# Electronics_Design_V2_v8.net
KiCad netlist of a schematic drawn in EAGLE
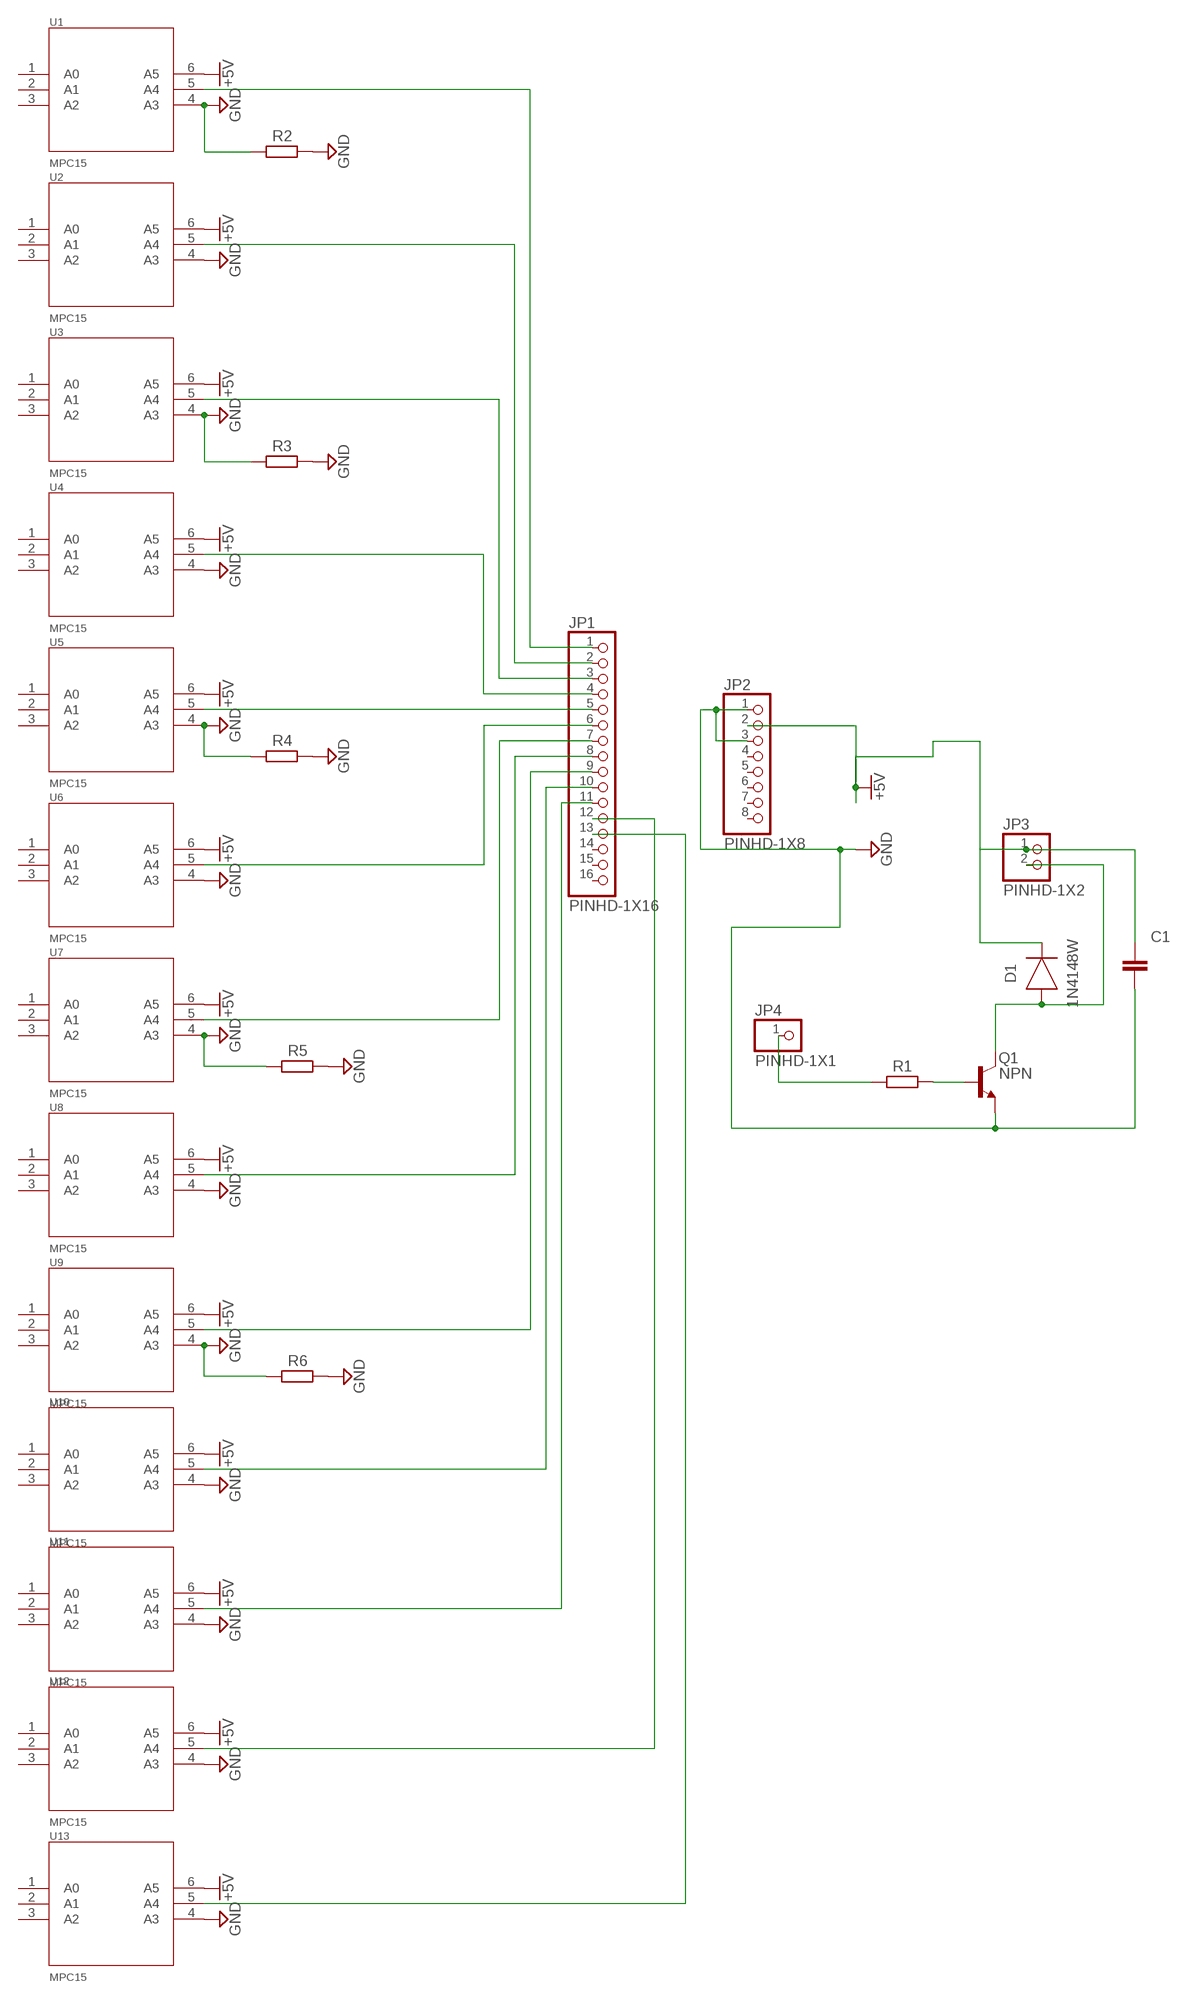
[diagram p0: schematic, sheet 1]

(export (version "E")
  (design (tool "Eeschema 10.0.6"))
  (components
    (comp (ref "C1")
      (value "C_CHIP-1206(3216-METRIC)")
      (footprint "eagle-import:CAPC3216X135")
      (libsource (lib "eagle-import") (part "CCHIP-1206(3216-METRIC)_"))
    )
    (comp (ref "D1")
      (value "1N4148W")
      (footprint "eagle-import:SOD3715X135")
      (fields (field (name "MANUFACTURER") "Diodes Incorporated"))
      (libsource (lib "eagle-import") (part "DIODE__SOD123G1N4148W-7-F"))
    )
    (comp (ref "JP1")
      (value "PINHD-1X16")
      (footprint "eagle-import:1X16")
      (libsource (lib "eagle-import") (part "PINHD-1X16"))
    )
    (comp (ref "JP2")
      (value "PINHD-1X8")
      (footprint "eagle-import:1X08")
      (libsource (lib "eagle-import") (part "PINHD-1X8"))
    )
    (comp (ref "JP3")
      (value "PINHD-1X2")
      (footprint "eagle-import:1X02")
      (libsource (lib "eagle-import") (part "PINHD-1X2"))
    )
    (comp (ref "JP4")
      (value "PINHD-1X1")
      (footprint "eagle-import:1X01")
      (libsource (lib "eagle-import") (part "PINHD-1X1"))
    )
    (comp (ref "Q1")
      (value "NPN")
      (footprint "eagle-import:SC59")
      (libsource (lib "eagle-import") (part "NPNSC-59_"))
    )
    (comp (ref "R1")
      (value "R_CHIP-1206(3216-METRIC)")
      (footprint "eagle-import:RESC3216X70")
      (libsource (lib "eagle-import") (part "RCHIP-1206(3216-METRIC)_"))
    )
    (comp (ref "R2")
      (value "R_CHIP-1206(3216-METRIC)")
      (footprint "eagle-import:RESC3216X70")
      (libsource (lib "eagle-import") (part "RCHIP-1206(3216-METRIC)_"))
    )
    (comp (ref "R3")
      (value "R_CHIP-1206(3216-METRIC)")
      (footprint "eagle-import:RESC3216X70")
      (libsource (lib "eagle-import") (part "RCHIP-1206(3216-METRIC)_"))
    )
    (comp (ref "R4")
      (value "R_CHIP-1206(3216-METRIC)")
      (footprint "eagle-import:RESC3216X70")
      (libsource (lib "eagle-import") (part "RCHIP-1206(3216-METRIC)_"))
    )
    (comp (ref "R5")
      (value "R_CHIP-1206(3216-METRIC)")
      (footprint "eagle-import:RESC3216X70")
      (libsource (lib "eagle-import") (part "RCHIP-1206(3216-METRIC)_"))
    )
    (comp (ref "R6")
      (value "R_CHIP-1206(3216-METRIC)")
      (footprint "eagle-import:RESC3216X70")
      (libsource (lib "eagle-import") (part "RCHIP-1206(3216-METRIC)_"))
    )
    (comp (ref "U1")
      (value "MPC15")
      (footprint "eagle-import:DIP1000W53P254L850H340Q6B")
      (libsource (lib "eagle-import") (part "MPC15"))
    )
    (comp (ref "U2")
      (value "MPC15")
      (footprint "eagle-import:DIP1000W53P254L850H340Q6B")
      (libsource (lib "eagle-import") (part "MPC15"))
    )
    (comp (ref "U3")
      (value "MPC15")
      (footprint "eagle-import:DIP1000W53P254L850H340Q6B")
      (libsource (lib "eagle-import") (part "MPC15"))
    )
    (comp (ref "U4")
      (value "MPC15")
      (footprint "eagle-import:DIP1000W53P254L850H340Q6B")
      (libsource (lib "eagle-import") (part "MPC15"))
    )
    (comp (ref "U5")
      (value "MPC15")
      (footprint "eagle-import:DIP1000W53P254L850H340Q6B")
      (libsource (lib "eagle-import") (part "MPC15"))
    )
    (comp (ref "U6")
      (value "MPC15")
      (footprint "eagle-import:DIP1000W53P254L850H340Q6B")
      (libsource (lib "eagle-import") (part "MPC15"))
    )
    (comp (ref "U7")
      (value "MPC15")
      (footprint "eagle-import:DIP1000W53P254L850H340Q6B")
      (libsource (lib "eagle-import") (part "MPC15"))
    )
    (comp (ref "U8")
      (value "MPC15")
      (footprint "eagle-import:DIP1000W53P254L850H340Q6B")
      (libsource (lib "eagle-import") (part "MPC15"))
    )
    (comp (ref "U9")
      (value "MPC15")
      (footprint "eagle-import:DIP1000W53P254L850H340Q6B")
      (libsource (lib "eagle-import") (part "MPC15"))
    )
    (comp (ref "U10")
      (value "MPC15")
      (footprint "eagle-import:DIP1000W53P254L850H340Q6B")
      (libsource (lib "eagle-import") (part "MPC15"))
    )
    (comp (ref "U11")
      (value "MPC15")
      (footprint "eagle-import:DIP1000W53P254L850H340Q6B")
      (libsource (lib "eagle-import") (part "MPC15"))
    )
    (comp (ref "U12")
      (value "MPC15")
      (footprint "eagle-import:DIP1000W53P254L850H340Q6B")
      (libsource (lib "eagle-import") (part "MPC15"))
    )
    (comp (ref "U13")
      (value "MPC15")
      (footprint "eagle-import:DIP1000W53P254L850H340Q6B")
      (libsource (lib "eagle-import") (part "MPC15"))
    )
  )
  (nets
    (net (code "1") (name "+5V") (class "Default")
      (node (ref "C1") (pin "1") (pinfunction "1_1") (pintype "passive"))
      (node (ref "D1") (pin "1") (pinfunction "C_1") (pintype "passive"))
      (node (ref "JP2") (pin "2") (pinfunction "2_2") (pintype "passive"))
      (node (ref "JP3") (pin "1") (pinfunction "1_1") (pintype "passive"))
      (node (ref "U1") (pin "6") (pinfunction "A5_6") (pintype "power_in"))
      (node (ref "U10") (pin "6") (pinfunction "A5_6") (pintype "power_in"))
      (node (ref "U11") (pin "6") (pinfunction "A5_6") (pintype "power_in"))
      (node (ref "U12") (pin "6") (pinfunction "A5_6") (pintype "power_in"))
      (node (ref "U13") (pin "6") (pinfunction "A5_6") (pintype "power_in"))
      (node (ref "U2") (pin "6") (pinfunction "A5_6") (pintype "power_in"))
      (node (ref "U3") (pin "6") (pinfunction "A5_6") (pintype "power_in"))
      (node (ref "U4") (pin "6") (pinfunction "A5_6") (pintype "power_in"))
      (node (ref "U5") (pin "6") (pinfunction "A5_6") (pintype "power_in"))
      (node (ref "U6") (pin "6") (pinfunction "A5_6") (pintype "power_in"))
      (node (ref "U7") (pin "6") (pinfunction "A5_6") (pintype "power_in"))
      (node (ref "U8") (pin "6") (pinfunction "A5_6") (pintype "power_in"))
      (node (ref "U9") (pin "6") (pinfunction "A5_6") (pintype "power_in"))
    )
    (net (code "2") (name "GND") (class "Default")
      (node (ref "C1") (pin "2") (pinfunction "2_2") (pintype "passive"))
      (node (ref "JP2") (pin "1") (pinfunction "1_1") (pintype "passive"))
      (node (ref "JP2") (pin "3") (pinfunction "3_3") (pintype "passive"))
      (node (ref "Q1") (pin "E") (pinfunction "E_E") (pintype "passive"))
      (node (ref "R2") (pin "1") (pinfunction "1_1") (pintype "passive"))
      (node (ref "R2") (pin "2") (pinfunction "2_2") (pintype "passive"))
      (node (ref "R3") (pin "1") (pinfunction "1_1") (pintype "passive"))
      (node (ref "R3") (pin "2") (pinfunction "2_2") (pintype "passive"))
      (node (ref "R4") (pin "1") (pinfunction "1_1") (pintype "passive"))
      (node (ref "R4") (pin "2") (pinfunction "2_2") (pintype "passive"))
      (node (ref "R5") (pin "1") (pinfunction "1_1") (pintype "passive"))
      (node (ref "R5") (pin "2") (pinfunction "2_2") (pintype "passive"))
      (node (ref "R6") (pin "1") (pinfunction "1_1") (pintype "passive"))
      (node (ref "R6") (pin "2") (pinfunction "2_2") (pintype "passive"))
      (node (ref "U1") (pin "4") (pinfunction "A3_4") (pintype "power_in"))
      (node (ref "U10") (pin "4") (pinfunction "A3_4") (pintype "power_in"))
      (node (ref "U11") (pin "4") (pinfunction "A3_4") (pintype "power_in"))
      (node (ref "U12") (pin "4") (pinfunction "A3_4") (pintype "power_in"))
      (node (ref "U13") (pin "4") (pinfunction "A3_4") (pintype "power_in"))
      (node (ref "U2") (pin "4") (pinfunction "A3_4") (pintype "power_in"))
      (node (ref "U3") (pin "4") (pinfunction "A3_4") (pintype "power_in"))
      (node (ref "U4") (pin "4") (pinfunction "A3_4") (pintype "power_in"))
      (node (ref "U5") (pin "4") (pinfunction "A3_4") (pintype "power_in"))
      (node (ref "U6") (pin "4") (pinfunction "A3_4") (pintype "power_in"))
      (node (ref "U7") (pin "4") (pinfunction "A3_4") (pintype "power_in"))
      (node (ref "U8") (pin "4") (pinfunction "A3_4") (pintype "power_in"))
      (node (ref "U9") (pin "4") (pinfunction "A3_4") (pintype "power_in"))
    )
    (net (code "3") (name "Net-(D1-A)") (class "Default")
      (node (ref "D1") (pin "2") (pinfunction "A_2") (pintype "passive"))
      (node (ref "JP3") (pin "2") (pinfunction "2_2") (pintype "passive"))
      (node (ref "Q1") (pin "C") (pinfunction "C_C") (pintype "passive"))
    )
    (net (code "4") (name "Net-(JP4-Pad1)") (class "Default")
      (node (ref "JP4") (pin "1") (pinfunction "1_1") (pintype "passive"))
      (node (ref "R1") (pin "1") (pinfunction "1_1") (pintype "passive"))
    )
    (net (code "5") (name "Net-(Q1-PadB)") (class "Default")
      (node (ref "Q1") (pin "B") (pinfunction "B_B") (pintype "passive"))
      (node (ref "R1") (pin "2") (pinfunction "2_2") (pintype "passive"))
    )
    (net (code "6") (name "Net-(U1-A4)") (class "Default")
      (node (ref "JP1") (pin "1") (pinfunction "1_1") (pintype "passive"))
      (node (ref "U1") (pin "5") (pinfunction "A4_5") (pintype "output"))
    )
    (net (code "7") (name "Net-(U2-A4)") (class "Default")
      (node (ref "JP1") (pin "2") (pinfunction "2_2") (pintype "passive"))
      (node (ref "U2") (pin "5") (pinfunction "A4_5") (pintype "output"))
    )
    (net (code "8") (name "Net-(U3-A4)") (class "Default")
      (node (ref "JP1") (pin "3") (pinfunction "3_3") (pintype "passive"))
      (node (ref "U3") (pin "5") (pinfunction "A4_5") (pintype "output"))
    )
    (net (code "9") (name "Net-(U4-A4)") (class "Default")
      (node (ref "JP1") (pin "4") (pinfunction "4_4") (pintype "passive"))
      (node (ref "U4") (pin "5") (pinfunction "A4_5") (pintype "output"))
    )
    (net (code "10") (name "Net-(U5-A4)") (class "Default")
      (node (ref "JP1") (pin "5") (pinfunction "5_5") (pintype "passive"))
      (node (ref "U5") (pin "5") (pinfunction "A4_5") (pintype "output"))
    )
    (net (code "11") (name "Net-(U6-A4)") (class "Default")
      (node (ref "JP1") (pin "6") (pinfunction "6_6") (pintype "passive"))
      (node (ref "U6") (pin "5") (pinfunction "A4_5") (pintype "output"))
    )
    (net (code "12") (name "Net-(U7-A4)") (class "Default")
      (node (ref "JP1") (pin "7") (pinfunction "7_7") (pintype "passive"))
      (node (ref "U7") (pin "5") (pinfunction "A4_5") (pintype "output"))
    )
    (net (code "13") (name "Net-(U8-A4)") (class "Default")
      (node (ref "JP1") (pin "8") (pinfunction "8_8") (pintype "passive"))
      (node (ref "U8") (pin "5") (pinfunction "A4_5") (pintype "output"))
    )
    (net (code "14") (name "Net-(U9-A4)") (class "Default")
      (node (ref "JP1") (pin "9") (pinfunction "9_9") (pintype "passive"))
      (node (ref "U9") (pin "5") (pinfunction "A4_5") (pintype "output"))
    )
    (net (code "15") (name "Net-(U10-A4)") (class "Default")
      (node (ref "JP1") (pin "10") (pinfunction "10_10") (pintype "passive"))
      (node (ref "U10") (pin "5") (pinfunction "A4_5") (pintype "output"))
    )
    (net (code "16") (name "Net-(U11-A4)") (class "Default")
      (node (ref "JP1") (pin "11") (pinfunction "11_11") (pintype "passive"))
      (node (ref "U11") (pin "5") (pinfunction "A4_5") (pintype "output"))
    )
    (net (code "17") (name "Net-(U12-A4)") (class "Default")
      (node (ref "JP1") (pin "12") (pinfunction "12_12") (pintype "passive"))
      (node (ref "U12") (pin "5") (pinfunction "A4_5") (pintype "output"))
    )
    (net (code "18") (name "Net-(U13-A4)") (class "Default")
      (node (ref "JP1") (pin "13") (pinfunction "13_13") (pintype "passive"))
      (node (ref "U13") (pin "5") (pinfunction "A4_5") (pintype "output"))
    )
    (net (code "19") (name "unconnected-(JP1-Pad14)") (class "Default")
      (node (ref "JP1") (pin "14") (pinfunction "14_14") (pintype "passive"))
    )
    (net (code "20") (name "unconnected-(JP1-Pad15)") (class "Default")
      (node (ref "JP1") (pin "15") (pinfunction "15_15") (pintype "passive"))
    )
    (net (code "21") (name "unconnected-(JP1-Pad16)") (class "Default")
      (node (ref "JP1") (pin "16") (pinfunction "16_16") (pintype "passive"))
    )
    (net (code "22") (name "unconnected-(JP2-Pad4)") (class "Default")
      (node (ref "JP2") (pin "4") (pinfunction "4_4") (pintype "passive"))
    )
    (net (code "23") (name "unconnected-(JP2-Pad5)") (class "Default")
      (node (ref "JP2") (pin "5") (pinfunction "5_5") (pintype "passive"))
    )
    (net (code "24") (name "unconnected-(JP2-Pad6)") (class "Default")
      (node (ref "JP2") (pin "6") (pinfunction "6_6") (pintype "passive"))
    )
    (net (code "25") (name "unconnected-(JP2-Pad7)") (class "Default")
      (node (ref "JP2") (pin "7") (pinfunction "7_7") (pintype "passive"))
    )
    (net (code "26") (name "unconnected-(JP2-Pad8)") (class "Default")
      (node (ref "JP2") (pin "8") (pinfunction "8_8") (pintype "passive"))
    )
    (net (code "27") (name "unconnected-(U1-A0-Pad1)") (class "Default")
      (node (ref "U1") (pin "1") (pinfunction "A0_1") (pintype "no_connect"))
    )
    (net (code "28") (name "unconnected-(U1-A1-Pad2)") (class "Default")
      (node (ref "U1") (pin "2") (pinfunction "A1_2") (pintype "no_connect"))
    )
    (net (code "29") (name "unconnected-(U1-A2-Pad3)") (class "Default")
      (node (ref "U1") (pin "3") (pinfunction "A2_3") (pintype "no_connect"))
    )
    (net (code "30") (name "unconnected-(U2-A0-Pad1)") (class "Default")
      (node (ref "U2") (pin "1") (pinfunction "A0_1") (pintype "no_connect"))
    )
    (net (code "31") (name "unconnected-(U2-A1-Pad2)") (class "Default")
      (node (ref "U2") (pin "2") (pinfunction "A1_2") (pintype "no_connect"))
    )
    (net (code "32") (name "unconnected-(U2-A2-Pad3)") (class "Default")
      (node (ref "U2") (pin "3") (pinfunction "A2_3") (pintype "no_connect"))
    )
    (net (code "33") (name "unconnected-(U3-A0-Pad1)") (class "Default")
      (node (ref "U3") (pin "1") (pinfunction "A0_1") (pintype "no_connect"))
    )
    (net (code "34") (name "unconnected-(U3-A1-Pad2)") (class "Default")
      (node (ref "U3") (pin "2") (pinfunction "A1_2") (pintype "no_connect"))
    )
    (net (code "35") (name "unconnected-(U3-A2-Pad3)") (class "Default")
      (node (ref "U3") (pin "3") (pinfunction "A2_3") (pintype "no_connect"))
    )
    (net (code "36") (name "unconnected-(U4-A0-Pad1)") (class "Default")
      (node (ref "U4") (pin "1") (pinfunction "A0_1") (pintype "no_connect"))
    )
    (net (code "37") (name "unconnected-(U4-A1-Pad2)") (class "Default")
      (node (ref "U4") (pin "2") (pinfunction "A1_2") (pintype "no_connect"))
    )
    (net (code "38") (name "unconnected-(U4-A2-Pad3)") (class "Default")
      (node (ref "U4") (pin "3") (pinfunction "A2_3") (pintype "no_connect"))
    )
    (net (code "39") (name "unconnected-(U5-A0-Pad1)") (class "Default")
      (node (ref "U5") (pin "1") (pinfunction "A0_1") (pintype "no_connect"))
    )
    (net (code "40") (name "unconnected-(U5-A1-Pad2)") (class "Default")
      (node (ref "U5") (pin "2") (pinfunction "A1_2") (pintype "no_connect"))
    )
    (net (code "41") (name "unconnected-(U5-A2-Pad3)") (class "Default")
      (node (ref "U5") (pin "3") (pinfunction "A2_3") (pintype "no_connect"))
    )
    (net (code "42") (name "unconnected-(U6-A0-Pad1)") (class "Default")
      (node (ref "U6") (pin "1") (pinfunction "A0_1") (pintype "no_connect"))
    )
    (net (code "43") (name "unconnected-(U6-A1-Pad2)") (class "Default")
      (node (ref "U6") (pin "2") (pinfunction "A1_2") (pintype "no_connect"))
    )
    (net (code "44") (name "unconnected-(U6-A2-Pad3)") (class "Default")
      (node (ref "U6") (pin "3") (pinfunction "A2_3") (pintype "no_connect"))
    )
    (net (code "45") (name "unconnected-(U7-A0-Pad1)") (class "Default")
      (node (ref "U7") (pin "1") (pinfunction "A0_1") (pintype "no_connect"))
    )
    (net (code "46") (name "unconnected-(U7-A1-Pad2)") (class "Default")
      (node (ref "U7") (pin "2") (pinfunction "A1_2") (pintype "no_connect"))
    )
    (net (code "47") (name "unconnected-(U7-A2-Pad3)") (class "Default")
      (node (ref "U7") (pin "3") (pinfunction "A2_3") (pintype "no_connect"))
    )
    (net (code "48") (name "unconnected-(U8-A0-Pad1)") (class "Default")
      (node (ref "U8") (pin "1") (pinfunction "A0_1") (pintype "no_connect"))
    )
    (net (code "49") (name "unconnected-(U8-A1-Pad2)") (class "Default")
      (node (ref "U8") (pin "2") (pinfunction "A1_2") (pintype "no_connect"))
    )
    (net (code "50") (name "unconnected-(U8-A2-Pad3)") (class "Default")
      (node (ref "U8") (pin "3") (pinfunction "A2_3") (pintype "no_connect"))
    )
    (net (code "51") (name "unconnected-(U9-A0-Pad1)") (class "Default")
      (node (ref "U9") (pin "1") (pinfunction "A0_1") (pintype "no_connect"))
    )
    (net (code "52") (name "unconnected-(U9-A1-Pad2)") (class "Default")
      (node (ref "U9") (pin "2") (pinfunction "A1_2") (pintype "no_connect"))
    )
    (net (code "53") (name "unconnected-(U9-A2-Pad3)") (class "Default")
      (node (ref "U9") (pin "3") (pinfunction "A2_3") (pintype "no_connect"))
    )
    (net (code "54") (name "unconnected-(U10-A0-Pad1)") (class "Default")
      (node (ref "U10") (pin "1") (pinfunction "A0_1") (pintype "no_connect"))
    )
    (net (code "55") (name "unconnected-(U10-A1-Pad2)") (class "Default")
      (node (ref "U10") (pin "2") (pinfunction "A1_2") (pintype "no_connect"))
    )
    (net (code "56") (name "unconnected-(U10-A2-Pad3)") (class "Default")
      (node (ref "U10") (pin "3") (pinfunction "A2_3") (pintype "no_connect"))
    )
    (net (code "57") (name "unconnected-(U11-A0-Pad1)") (class "Default")
      (node (ref "U11") (pin "1") (pinfunction "A0_1") (pintype "no_connect"))
    )
    (net (code "58") (name "unconnected-(U11-A1-Pad2)") (class "Default")
      (node (ref "U11") (pin "2") (pinfunction "A1_2") (pintype "no_connect"))
    )
    (net (code "59") (name "unconnected-(U11-A2-Pad3)") (class "Default")
      (node (ref "U11") (pin "3") (pinfunction "A2_3") (pintype "no_connect"))
    )
    (net (code "60") (name "unconnected-(U12-A0-Pad1)") (class "Default")
      (node (ref "U12") (pin "1") (pinfunction "A0_1") (pintype "no_connect"))
    )
    (net (code "61") (name "unconnected-(U12-A1-Pad2)") (class "Default")
      (node (ref "U12") (pin "2") (pinfunction "A1_2") (pintype "no_connect"))
    )
    (net (code "62") (name "unconnected-(U12-A2-Pad3)") (class "Default")
      (node (ref "U12") (pin "3") (pinfunction "A2_3") (pintype "no_connect"))
    )
    (net (code "63") (name "unconnected-(U13-A0-Pad1)") (class "Default")
      (node (ref "U13") (pin "1") (pinfunction "A0_1") (pintype "no_connect"))
    )
    (net (code "64") (name "unconnected-(U13-A1-Pad2)") (class "Default")
      (node (ref "U13") (pin "2") (pinfunction "A1_2") (pintype "no_connect"))
    )
    (net (code "65") (name "unconnected-(U13-A2-Pad3)") (class "Default")
      (node (ref "U13") (pin "3") (pinfunction "A2_3") (pintype "no_connect"))
    )
  )
)
